# MotoLogger_v3_4_Schematic.net
KiCad netlist of a schematic drawn in EasyEDA
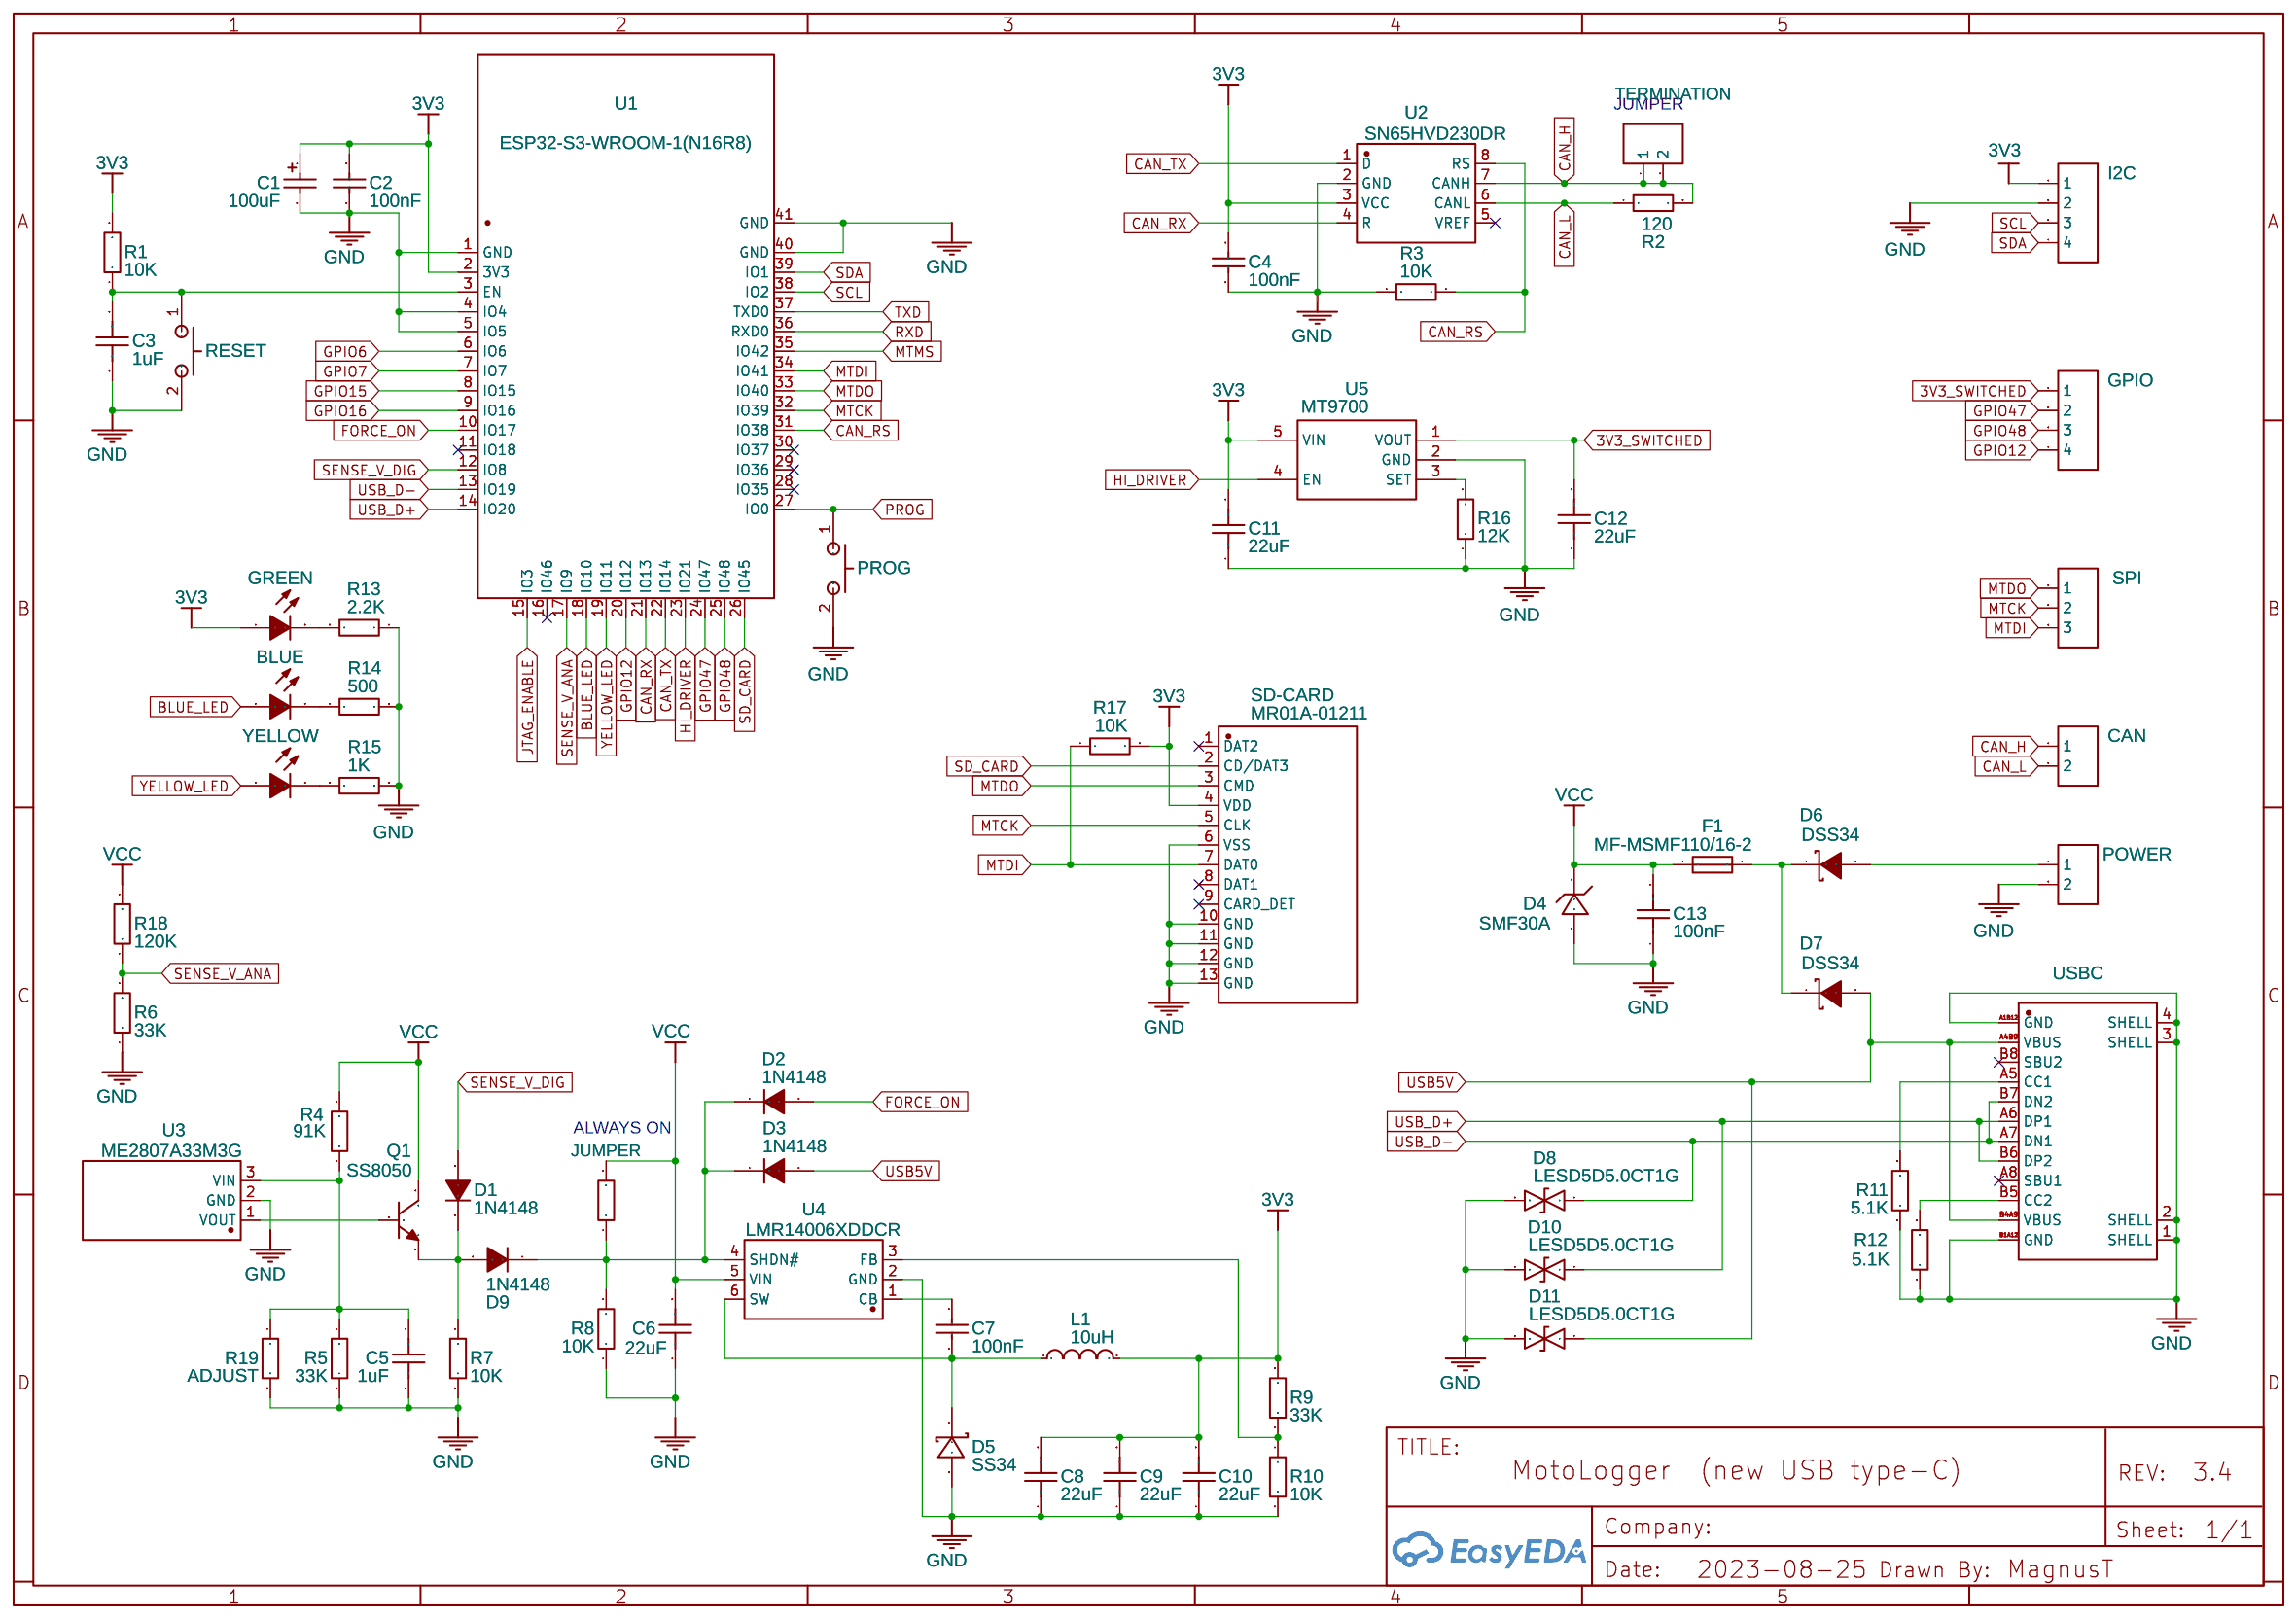
[diagram p0: schematic sheet]

(export (version "E")
  (design (tool "Eeschema 10.0.6"))
  (components
    (comp (ref "BLUE")
      (value "19-217/BHC-ZL1M2RY/3T")
      (fields (field (name "Manufacturer") "EVERLIGHT"))
      (libsource (lib "") (part "19-217/BHC-ZL1M2RY/3T"))
    )
    (comp (ref "C1")
      (value "100uF")
      (fields (field (name "Manufacturer Part") "TAJB107K006RNJ") (field (name "Manufacturer") "AVX"))
      (libsource (lib "") (part "TAJB107K006RNJ"))
    )
    (comp (ref "C2")
      (value "100nF")
      (fields (field (name "Manufacturer Part") "CL05B104KO5NNNC") (field (name "Manufacturer") "SAMSUNG"))
      (libsource (lib "") (part "CL05B104KO5NNNC"))
    )
    (comp (ref "C3")
      (value "1uF")
      (fields (field (name "Manufacturer Part") "CL05A105KA5NQNC") (field (name "Manufacturer") "SAMSUNG"))
      (libsource (lib "") (part "CL05A105KA5NQNC_1"))
    )
    (comp (ref "C4")
      (value "100nF")
      (fields (field (name "Manufacturer Part") "CL05B104KO5NNNC") (field (name "Manufacturer") "SAMSUNG"))
      (libsource (lib "") (part "CL05B104KO5NNNC"))
    )
    (comp (ref "C5")
      (value "1uF")
      (fields (field (name "Manufacturer Part") "CL05A105KA5NQNC") (field (name "Manufacturer") "SAMSUNG"))
      (libsource (lib "") (part "CL05A105KA5NQNC"))
    )
    (comp (ref "C6")
      (value "22uF")
      (fields
        (field (name "Manufacturer Part") "CL21A226MAYNNNE")
        (field (name "Manufacturer") "Samsung Electro-Mechanics")
      )
      (libsource (lib "") (part "CL21A226MAYNNNE"))
    )
    (comp (ref "C7")
      (value "100nF")
      (fields (field (name "Manufacturer Part") "CL05B104KO5NNNC") (field (name "Manufacturer") "SAMSUNG"))
      (libsource (lib "") (part "CL05B104KO5NNNC"))
    )
    (comp (ref "C8")
      (value "22uF")
      (fields (field (name "Manufacturer Part") "CL10A226MQ8NRNC") (field (name "Manufacturer") "SAMSUNG"))
      (libsource (lib "") (part "CL10A226MQ8NRNC"))
    )
    (comp (ref "C9")
      (value "22uF")
      (fields (field (name "Manufacturer Part") "CL10A226MQ8NRNC") (field (name "Manufacturer") "SAMSUNG"))
      (libsource (lib "") (part "CL10A226MQ8NRNC"))
    )
    (comp (ref "C10")
      (value "22uF")
      (fields (field (name "Manufacturer Part") "CL10A226MQ8NRNC") (field (name "Manufacturer") "SAMSUNG"))
      (libsource (lib "") (part "CL10A226MQ8NRNC"))
    )
    (comp (ref "C11")
      (value "22uF")
      (fields (field (name "Manufacturer Part") "CL10A226MQ8NRNC") (field (name "Manufacturer") "SAMSUNG"))
      (libsource (lib "") (part "CL10A226MQ8NRNC"))
    )
    (comp (ref "C12")
      (value "22uF")
      (fields (field (name "Manufacturer Part") "CL10A226MQ8NRNC") (field (name "Manufacturer") "SAMSUNG"))
      (libsource (lib "") (part "CL10A226MQ8NRNC"))
    )
    (comp (ref "C13")
      (value "100nF")
      (fields
        (field (name "Manufacturer Part") "CL05B104KB54PNC")
        (field (name "Manufacturer") "Samsung Electro-Mechanics")
      )
      (libsource (lib "") (part "CL05B104KB54PNC"))
    )
    (comp (ref "CAN") (value "HDR-M-2.54_1x2") (libsource (lib "") (part "HDR-M-2.54_1x2")))
    (comp (ref "D1")
      (value "1N4148")
      (fields (field (name "Manufacturer Part") "1N4148WS T4") (field (name "Manufacturer") "CJ"))
      (libsource (lib "") (part "1N4148WS T4_2"))
    )
    (comp (ref "D2")
      (value "1N4148")
      (fields (field (name "Manufacturer Part") "1N4148WS T4") (field (name "Manufacturer") "CJ"))
      (libsource (lib "") (part "1N4148WS T4_1"))
    )
    (comp (ref "D3")
      (value "1N4148")
      (fields (field (name "Manufacturer Part") "1N4148WS T4") (field (name "Manufacturer") "CJ"))
      (libsource (lib "") (part "1N4148WS T4_1"))
    )
    (comp (ref "D4")
      (value "SMF30A")
      (fields (field (name "Manufacturer") "DOWO"))
      (libsource (lib "") (part "SMF30A_C366558"))
    )
    (comp (ref "D5")
      (value "SS34")
      (fields (field (name "Manufacturer") "MDD"))
      (libsource (lib "") (part "SS34_C8678"))
    )
    (comp (ref "D6")
      (value "DSS34")
      (fields (field (name "Manufacturer") "STARSEA"))
      (libsource (lib "") (part "DSS34"))
    )
    (comp (ref "D7")
      (value "DSS34")
      (fields (field (name "Manufacturer") "STARSEA"))
      (libsource (lib "") (part "DSS34"))
    )
    (comp (ref "D8")
      (value "LESD5D5.0CT1G")
      (fields (field (name "Manufacturer") "Leshan Radio"))
      (libsource (lib "") (part "LESD5D5.0CT1G"))
    )
    (comp (ref "D9")
      (value "1N4148")
      (fields (field (name "Manufacturer Part") "1N4148WS T4") (field (name "Manufacturer") "CJ"))
      (libsource (lib "") (part "1N4148WS T4"))
    )
    (comp (ref "D10")
      (value "LESD5D5.0CT1G")
      (fields (field (name "Manufacturer") "Leshan Radio"))
      (libsource (lib "") (part "LESD5D5.0CT1G"))
    )
    (comp (ref "D11")
      (value "LESD5D5.0CT1G")
      (fields (field (name "Manufacturer") "Leshan Radio"))
      (libsource (lib "") (part "LESD5D5.0CT1G"))
    )
    (comp (ref "F1")
      (value "MF-MSMF110/16-2")
      (fields (field (name "Manufacturer") "BOURNS"))
      (libsource (lib "") (part "MF-MSMF110/16-2"))
    )
    (comp (ref "GPIO") (value "HDR-M-2.54_1x4") (libsource (lib "") (part "HDR-M-2.54_1x4")))
    (comp (ref "GREEN")
      (value "19-217/GHC-YR1S2/3T")
      (fields (field (name "Manufacturer") "EVERLIGHT"))
      (libsource (lib "") (part "19-217/GHC-YR1S2/3T"))
    )
    (comp (ref "I2C") (value "HDR-M-2.54_1x4") (libsource (lib "") (part "HDR-M-2.54_1x4_1")))
    (comp (ref "JUMPER") (value "-") (libsource (lib "") (part "0402WGF3092TCE")))
    (comp (ref "L1")
      (value "10uH")
      (fields
        (field (name "Manufacturer Part") "SLP6028S100MTT")
        (field (name "Manufacturer") "Sunltech Tech")
      )
      (libsource (lib "") (part "SLP6028S100MTT"))
    )
    (comp (ref "POWER") (value "HDR-M-2.54_1x2") (libsource (lib "") (part "HDR-M-2.54_1x2_2")))
    (comp (ref "PROG")
      (value "GT-TC029B-H025-L1N")
      (fields (field (name "Manufacturer") "G-Switch"))
      (libsource (lib "") (part "GT-TC029B-H025-L1N_1"))
    )
    (comp (ref "Q1")
      (value "SS8050")
      (fields (field (name "Manufacturer") "CJ"))
      (libsource (lib "") (part "SS8050_C2150"))
    )
    (comp (ref "R1")
      (value "10K")
      (fields (field (name "Manufacturer Part") "0402WGF1002TCE") (field (name "Manufacturer") "UniOhm"))
      (libsource (lib "") (part "0402WGF1002TCE_2"))
    )
    (comp (ref "R2")
      (value "120")
      (fields (field (name "Manufacturer Part") "RTT061200FTP") (field (name "Manufacturer") "RALEC"))
      (libsource (lib "") (part "RTT061200FTP"))
    )
    (comp (ref "R3")
      (value "10K")
      (fields (field (name "Manufacturer Part") "0402WGF1002TCE") (field (name "Manufacturer") "UniOhm"))
      (libsource (lib "") (part "0402WGF1002TCE"))
    )
    (comp (ref "R4")
      (value "91K")
      (fields (field (name "Manufacturer Part") "0402WGF9102TCE") (field (name "Manufacturer") "UniOhm"))
      (libsource (lib "") (part "0402WGF9102TCE_1"))
    )
    (comp (ref "R5")
      (value "33K")
      (fields (field (name "Manufacturer Part") "0402WGF3302TCE") (field (name "Manufacturer") "UniOhm"))
      (libsource (lib "") (part "0402WGF3302TCE"))
    )
    (comp (ref "R6")
      (value "33K")
      (fields (field (name "Manufacturer Part") "0402WGF3302TCE") (field (name "Manufacturer") "UniOhm"))
      (libsource (lib "") (part "0402WGF3302TCE"))
    )
    (comp (ref "R7")
      (value "10K")
      (fields (field (name "Manufacturer Part") "0402WGF1002TCE") (field (name "Manufacturer") "UniOhm"))
      (libsource (lib "") (part "0402WGF1002TCE_2"))
    )
    (comp (ref "R8")
      (value "10K")
      (fields (field (name "Manufacturer Part") "0402WGF1002TCE") (field (name "Manufacturer") "UniOhm"))
      (libsource (lib "") (part "0402WGF1002TCE_2"))
    )
    (comp (ref "R9")
      (value "33K")
      (fields (field (name "Manufacturer Part") "0402WGF3302TCE") (field (name "Manufacturer") "UniOhm"))
      (libsource (lib "") (part "0402WGF3302TCE"))
    )
    (comp (ref "R10")
      (value "10K")
      (fields (field (name "Manufacturer Part") "0402WGF1002TCE") (field (name "Manufacturer") "UniOhm"))
      (libsource (lib "") (part "0402WGF1002TCE_1"))
    )
    (comp (ref "R11")
      (value "5.1K")
      (fields (field (name "Manufacturer Part") "0402WGF5101TCE") (field (name "Manufacturer") "UniOhm"))
      (libsource (lib "") (part "0402WGF5101TCE"))
    )
    (comp (ref "R12")
      (value "5.1K")
      (fields (field (name "Manufacturer Part") "0402WGF5101TCE") (field (name "Manufacturer") "UniOhm"))
      (libsource (lib "") (part "0402WGF5101TCE"))
    )
    (comp (ref "R13")
      (value "2.2K")
      (fields (field (name "Manufacturer Part") "0402WGF2201TCE") (field (name "Manufacturer") "UniOhm"))
      (libsource (lib "") (part "0402WGF2201TCE"))
    )
    (comp (ref "R14")
      (value "500")
      (fields (field (name "Manufacturer Part") "0402WGF4700TCE") (field (name "Manufacturer") "UniOhm"))
      (libsource (lib "") (part "0402WGF1001TCE"))
    )
    (comp (ref "R15")
      (value "1K")
      (fields (field (name "Manufacturer Part") "0402WGF1001TCE") (field (name "Manufacturer") "UniOhm"))
      (libsource (lib "") (part "0402WGF1001TCE"))
    )
    (comp (ref "R16")
      (value "12K")
      (fields (field (name "Manufacturer Part") "0402WGF1202TCE") (field (name "Manufacturer") "UniOhm"))
      (libsource (lib "") (part "0402WGF1202TCE"))
    )
    (comp (ref "R17")
      (value "10K")
      (fields (field (name "Manufacturer Part") "0402WGF1002TCE") (field (name "Manufacturer") "UniOhm"))
      (libsource (lib "") (part "0402WGF1002TCE"))
    )
    (comp (ref "R18")
      (value "120K")
      (fields (field (name "Manufacturer Part") "0402WGF1203TCE") (field (name "Manufacturer") "UniOhm"))
      (libsource (lib "") (part "0402WGF1203TCE"))
    )
    (comp (ref "R19")
      (value "ADJUST")
      (fields (field (name "Manufacturer Part") "0402WGF9102TCE") (field (name "Manufacturer") "UniOhm"))
      (libsource (lib "") (part "0402WGF9102TCE"))
    )
    (comp (ref "RESET")
      (value "GT-TC029B-H025-L1N")
      (fields (field (name "Manufacturer") "G-Switch"))
      (libsource (lib "") (part "GT-TC029B-H025-L1N"))
    )
    (comp (ref "SD-CARD")
      (value "MR01A-01211")
      (fields (field (name "Manufacturer") "ATOM(爱特姆)"))
      (libsource (lib "") (part "MR01A-01211"))
    )
    (comp (ref "SPI") (value "HDR-M-2.54_1x3") (libsource (lib "") (part "HDR-M-2.54_1x3")))
    (comp (ref "TERMINATION") (value "HDR-M-2.54_1x2") (libsource (lib "") (part "HDR-M-2.54_1x2_1")))
    (comp (ref "U1")
      (value "ESP32-S3-WROOM-1(N16R8)")
      (fields (field (name "Manufacturer") "ESPRESSIF(乐鑫)"))
      (libsource (lib "") (part "ESP32-S3-WROOM-1(N16R8)"))
    )
    (comp (ref "U2")
      (value "SN65HVD230DR")
      (fields (field (name "Manufacturer") "TI"))
      (libsource (lib "") (part "SN65HVD230DR"))
    )
    (comp (ref "U3")
      (value "ME2807A33M3G")
      (fields (field (name "Manufacturer") "Nanjing Micro One Elec"))
      (libsource (lib "") (part "ME2807A33M3G"))
    )
    (comp (ref "U4")
      (value "LMR14006XDDCR")
      (fields (field (name "Manufacturer") "Texas Instruments"))
      (libsource (lib "") (part "LMR14006XDDCR"))
    )
    (comp (ref "U5")
      (value "MT9700")
      (fields (field (name "Manufacturer") "AEROSEMI"))
      (libsource (lib "") (part "MT9700"))
    )
    (comp (ref "USBC")
      (value "GT-USB-7010ASV")
      (fields (field (name "Manufacturer") "G-Switch(品赞)"))
      (libsource (lib "") (part "GT-USB-7010ASV"))
    )
    (comp (ref "YELLOW")
      (value "19-213/Y2C-CQ2R2L/3T(CY)")
      (fields (field (name "Manufacturer") "EVERLIGHT"))
      (libsource (lib "") (part "19-213/Y2C-CQ2R2L/3T(CY)"))
    )
  )
  (nets
    (net (code "1") (name "3V3") (class "Default")
      (node (ref "C1") (pin "1") (pinfunction "1_1") (pintype "input"))
      (node (ref "C10") (pin "2") (pinfunction "2_2") (pintype "unspecified"))
      (node (ref "C11") (pin "2") (pinfunction "2_2") (pintype "unspecified"))
      (node (ref "C2") (pin "2") (pinfunction "2_2") (pintype "input"))
      (node (ref "C4") (pin "2") (pinfunction "2_2") (pintype "input"))
      (node (ref "C8") (pin "2") (pinfunction "2_2") (pintype "unspecified"))
      (node (ref "C9") (pin "2") (pinfunction "2_2") (pintype "unspecified"))
      (node (ref "GREEN") (pin "1") (pinfunction "A_1") (pintype "input"))
      (node (ref "I2C") (pin "1") (pinfunction "1_1") (pintype "unspecified"))
      (node (ref "L1") (pin "2") (pinfunction "2_2") (pintype "unspecified"))
      (node (ref "R1") (pin "2") (pinfunction "2_2") (pintype "input"))
      (node (ref "R17") (pin "2") (pinfunction "2_2") (pintype "input"))
      (node (ref "R9") (pin "2") (pinfunction "2_2") (pintype "input"))
      (node (ref "SD-CARD") (pin "4") (pinfunction "VDD_4") (pintype "unspecified"))
      (node (ref "U1") (pin "2") (pinfunction "3V3_2") (pintype "unspecified"))
      (node (ref "U2") (pin "3") (pinfunction "VCC_3") (pintype "unspecified"))
      (node (ref "U5") (pin "5") (pinfunction "VIN_5") (pintype "unspecified"))
    )
    (net (code "2") (name "3V3_SWITCHED") (class "Default")
      (node (ref "C12") (pin "2") (pinfunction "2_2") (pintype "unspecified"))
      (node (ref "GPIO") (pin "1") (pinfunction "1_1") (pintype "unspecified"))
      (node (ref "U5") (pin "1") (pinfunction "VOUT_1") (pintype "unspecified"))
    )
    (net (code "3") (name "BLUE_LED") (class "Default")
      (node (ref "BLUE") (pin "1") (pinfunction "A_1") (pintype "input"))
      (node (ref "U1") (pin "18") (pinfunction "IO10_18") (pintype "unspecified"))
    )
    (net (code "4") (name "CAN_H") (class "Default")
      (node (ref "CAN") (pin "1") (pinfunction "1_1") (pintype "unspecified"))
      (node (ref "R2") (pin "2") (pinfunction "2_2") (pintype "unspecified"))
      (node (ref "TERMINATION") (pin "1") (pinfunction "1_1") (pintype "unspecified"))
      (node (ref "TERMINATION") (pin "2") (pinfunction "2_2") (pintype "unspecified"))
      (node (ref "U2") (pin "7") (pinfunction "CANH_7") (pintype "unspecified"))
    )
    (net (code "5") (name "CAN_L") (class "Default")
      (node (ref "CAN") (pin "2") (pinfunction "2_2") (pintype "unspecified"))
      (node (ref "R2") (pin "1") (pinfunction "1_1") (pintype "unspecified"))
      (node (ref "U2") (pin "6") (pinfunction "CANL_6") (pintype "unspecified"))
    )
    (net (code "6") (name "CAN_RS") (class "Default")
      (node (ref "R3") (pin "2") (pinfunction "2_2") (pintype "input"))
      (node (ref "U1") (pin "31") (pinfunction "IO38_31") (pintype "unspecified"))
      (node (ref "U2") (pin "8") (pinfunction "RS_8") (pintype "unspecified"))
    )
    (net (code "7") (name "CAN_RX") (class "Default")
      (node (ref "U1") (pin "21") (pinfunction "IO13_21") (pintype "unspecified"))
      (node (ref "U2") (pin "4") (pinfunction "R_4") (pintype "unspecified"))
    )
    (net (code "8") (name "CAN_TX") (class "Default")
      (node (ref "U1") (pin "22") (pinfunction "IO14_22") (pintype "unspecified"))
      (node (ref "U2") (pin "1") (pinfunction "D_1") (pintype "unspecified"))
    )
    (net (code "9") (name "FORCE_ON") (class "Default")
      (node (ref "D2") (pin "2") (pinfunction "A_2") (pintype "unspecified"))
      (node (ref "U1") (pin "10") (pinfunction "IO17_10") (pintype "unspecified"))
    )
    (net (code "10") (name "GND") (class "Default")
      (node (ref "C1") (pin "2") (pinfunction "2_2") (pintype "input"))
      (node (ref "C10") (pin "1") (pinfunction "1_1") (pintype "unspecified"))
      (node (ref "C11") (pin "1") (pinfunction "1_1") (pintype "unspecified"))
      (node (ref "C12") (pin "1") (pinfunction "1_1") (pintype "unspecified"))
      (node (ref "C13") (pin "1") (pinfunction "1_1") (pintype "unspecified"))
      (node (ref "C2") (pin "1") (pinfunction "1_1") (pintype "input"))
      (node (ref "C3") (pin "1") (pinfunction "1_1") (pintype "unspecified"))
      (node (ref "C4") (pin "1") (pinfunction "1_1") (pintype "input"))
      (node (ref "C5") (pin "1") (pinfunction "1_1") (pintype "unspecified"))
      (node (ref "C6") (pin "1") (pinfunction "1_1") (pintype "unspecified"))
      (node (ref "C8") (pin "1") (pinfunction "1_1") (pintype "unspecified"))
      (node (ref "C9") (pin "1") (pinfunction "1_1") (pintype "unspecified"))
      (node (ref "D10") (pin "2") (pinfunction "2_2") (pintype "unspecified"))
      (node (ref "D11") (pin "2") (pinfunction "2_2") (pintype "unspecified"))
      (node (ref "D4") (pin "2") (pinfunction "2_2") (pintype "unspecified"))
      (node (ref "D5") (pin "2") (pinfunction "A_2") (pintype "unspecified"))
      (node (ref "D8") (pin "2") (pinfunction "2_2") (pintype "unspecified"))
      (node (ref "I2C") (pin "2") (pinfunction "2_2") (pintype "unspecified"))
      (node (ref "POWER") (pin "2") (pinfunction "2_2") (pintype "unspecified"))
      (node (ref "PROG") (pin "2") (pinfunction "2_2") (pintype "unspecified"))
      (node (ref "R10") (pin "2") (pinfunction "2_2") (pintype "input"))
      (node (ref "R11") (pin "1") (pinfunction "1_1") (pintype "input"))
      (node (ref "R12") (pin "1") (pinfunction "1_1") (pintype "input"))
      (node (ref "R13") (pin "1") (pinfunction "1_1") (pintype "input"))
      (node (ref "R14") (pin "2") (pinfunction "2_2") (pintype "input"))
      (node (ref "R15") (pin "2") (pinfunction "2_2") (pintype "input"))
      (node (ref "R16") (pin "1") (pinfunction "1_1") (pintype "input"))
      (node (ref "R19") (pin "2") (pinfunction "2_2") (pintype "input"))
      (node (ref "R3") (pin "1") (pinfunction "1_1") (pintype "input"))
      (node (ref "R5") (pin "1") (pinfunction "1_1") (pintype "input"))
      (node (ref "R6") (pin "1") (pinfunction "1_1") (pintype "input"))
      (node (ref "R7") (pin "1") (pinfunction "1_1") (pintype "input"))
      (node (ref "R8") (pin "1") (pinfunction "1_1") (pintype "input"))
      (node (ref "RESET") (pin "2") (pinfunction "2_2") (pintype "unspecified"))
      (node (ref "SD-CARD") (pin "10") (pinfunction "GND_10") (pintype "unspecified"))
      (node (ref "SD-CARD") (pin "11") (pinfunction "GND_11") (pintype "unspecified"))
      (node (ref "SD-CARD") (pin "12") (pinfunction "GND_12") (pintype "unspecified"))
      (node (ref "SD-CARD") (pin "13") (pinfunction "GND_13") (pintype "unspecified"))
      (node (ref "SD-CARD") (pin "6") (pinfunction "VSS_6") (pintype "unspecified"))
      (node (ref "U1") (pin "1") (pinfunction "GND_1") (pintype "unspecified"))
      (node (ref "U1") (pin "4") (pinfunction "IO4_4") (pintype "unspecified"))
      (node (ref "U1") (pin "40") (pinfunction "GND_40") (pintype "unspecified"))
      (node (ref "U1") (pin "41") (pinfunction "GND_41") (pintype "unspecified"))
      (node (ref "U1") (pin "5") (pinfunction "IO5_5") (pintype "unspecified"))
      (node (ref "U2") (pin "2") (pinfunction "GND_2") (pintype "unspecified"))
      (node (ref "U3") (pin "2") (pinfunction "GND_2") (pintype "unspecified"))
      (node (ref "U4") (pin "2") (pinfunction "GND_2") (pintype "unspecified"))
      (node (ref "U5") (pin "2") (pinfunction "GND_2") (pintype "unspecified"))
      (node (ref "USBC") (pin "1") (pinfunction "SHELL_1") (pintype "unspecified"))
      (node (ref "USBC") (pin "2") (pinfunction "SHELL_2") (pintype "unspecified"))
      (node (ref "USBC") (pin "3") (pinfunction "SHELL_3") (pintype "unspecified"))
      (node (ref "USBC") (pin "4") (pinfunction "SHELL_4") (pintype "unspecified"))
      (node (ref "USBC") (pin "A1B12") (pinfunction "GND_A1B12") (pintype "unspecified"))
      (node (ref "USBC") (pin "B1A12") (pinfunction "GND_B1A12") (pintype "unspecified"))
    )
    (net (code "11") (name "GPIO6") (class "Default")
      (node (ref "U1") (pin "6") (pinfunction "IO6_6") (pintype "unspecified"))
    )
    (net (code "12") (name "GPIO7") (class "Default")
      (node (ref "U1") (pin "7") (pinfunction "IO7_7") (pintype "unspecified"))
    )
    (net (code "13") (name "GPIO12") (class "Default")
      (node (ref "GPIO") (pin "4") (pinfunction "4_4") (pintype "unspecified"))
      (node (ref "U1") (pin "20") (pinfunction "IO12_20") (pintype "unspecified"))
    )
    (net (code "14") (name "GPIO15") (class "Default")
      (node (ref "U1") (pin "8") (pinfunction "IO15_8") (pintype "unspecified"))
    )
    (net (code "15") (name "GPIO16") (class "Default")
      (node (ref "U1") (pin "9") (pinfunction "IO16_9") (pintype "unspecified"))
    )
    (net (code "16") (name "GPIO47") (class "Default")
      (node (ref "GPIO") (pin "2") (pinfunction "2_2") (pintype "unspecified"))
      (node (ref "U1") (pin "24") (pinfunction "IO47_24") (pintype "unspecified"))
    )
    (net (code "17") (name "GPIO48") (class "Default")
      (node (ref "GPIO") (pin "3") (pinfunction "3_3") (pintype "unspecified"))
      (node (ref "U1") (pin "25") (pinfunction "IO48_25") (pintype "unspecified"))
    )
    (net (code "18") (name "HI_DRIVER") (class "Default")
      (node (ref "U1") (pin "23") (pinfunction "IO21_23") (pintype "unspecified"))
      (node (ref "U5") (pin "4") (pinfunction "EN_4") (pintype "unspecified"))
    )
    (net (code "19") (name "JTAG_ENABLE") (class "Default")
      (node (ref "U1") (pin "15") (pinfunction "IO3_15") (pintype "unspecified"))
    )
    (net (code "20") (name "MTCK") (class "Default")
      (node (ref "SD-CARD") (pin "5") (pinfunction "CLK_5") (pintype "unspecified"))
      (node (ref "SPI") (pin "2") (pinfunction "2_2") (pintype "input"))
      (node (ref "U1") (pin "32") (pinfunction "IO39_32") (pintype "unspecified"))
    )
    (net (code "21") (name "MTDI") (class "Default")
      (node (ref "R17") (pin "1") (pinfunction "1_1") (pintype "input"))
      (node (ref "SD-CARD") (pin "7") (pinfunction "DAT0_7") (pintype "unspecified"))
      (node (ref "SPI") (pin "3") (pinfunction "3_3") (pintype "input"))
      (node (ref "U1") (pin "34") (pinfunction "IO41_34") (pintype "unspecified"))
    )
    (net (code "22") (name "MTDO") (class "Default")
      (node (ref "SD-CARD") (pin "3") (pinfunction "CMD_3") (pintype "unspecified"))
      (node (ref "SPI") (pin "1") (pinfunction "1_1") (pintype "input"))
      (node (ref "U1") (pin "33") (pinfunction "IO40_33") (pintype "unspecified"))
    )
    (net (code "23") (name "MTMS") (class "Default")
      (node (ref "U1") (pin "35") (pinfunction "IO42_35") (pintype "unspecified"))
    )
    (net (code "24") (name "Net-(BLUE-C)") (class "Default")
      (node (ref "BLUE") (pin "2") (pinfunction "C_2") (pintype "input"))
      (node (ref "R14") (pin "1") (pinfunction "1_1") (pintype "input"))
    )
    (net (code "25") (name "Net-(D1-K)") (class "Default")
      (node (ref "D1") (pin "1") (pinfunction "K_1") (pintype "unspecified"))
      (node (ref "D9") (pin "2") (pinfunction "A_2") (pintype "unspecified"))
      (node (ref "Q1") (pin "2") (pinfunction "E_2") (pintype "unspecified"))
      (node (ref "R7") (pin "2") (pinfunction "2_2") (pintype "input"))
    )
    (net (code "26") (name "Net-(D2-K)") (class "Default")
      (node (ref "D2") (pin "1") (pinfunction "K_1") (pintype "unspecified"))
      (node (ref "D3") (pin "1") (pinfunction "K_1") (pintype "unspecified"))
      (node (ref "D9") (pin "1") (pinfunction "K_1") (pintype "unspecified"))
      (node (ref "JUMPER") (pin "1") (pinfunction "1_1") (pintype "unspecified"))
      (node (ref "R8") (pin "2") (pinfunction "2_2") (pintype "input"))
      (node (ref "U4") (pin "4") (pinfunction "SHDN#_4") (pintype "unspecified"))
    )
    (net (code "27") (name "Net-(D5-K)") (class "Default")
      (node (ref "C7") (pin "1") (pinfunction "1_1") (pintype "input"))
      (node (ref "D5") (pin "1") (pinfunction "K_1") (pintype "unspecified"))
      (node (ref "L1") (pin "1") (pinfunction "1_1") (pintype "unspecified"))
      (node (ref "U4") (pin "6") (pinfunction "SW_6") (pintype "unspecified"))
    )
    (net (code "28") (name "Net-(D6-A)") (class "Default")
      (node (ref "D6") (pin "2") (pinfunction "A_2") (pintype "unspecified"))
      (node (ref "POWER") (pin "1") (pinfunction "1_1") (pintype "unspecified"))
    )
    (net (code "29") (name "Net-(D6-K)") (class "Default")
      (node (ref "D6") (pin "1") (pinfunction "K_1") (pintype "unspecified"))
      (node (ref "D7") (pin "1") (pinfunction "K_1") (pintype "unspecified"))
      (node (ref "F1") (pin "2") (pinfunction "2_2") (pintype "unspecified"))
    )
    (net (code "30") (name "Net-(GREEN-C)") (class "Default")
      (node (ref "GREEN") (pin "2") (pinfunction "C_2") (pintype "input"))
      (node (ref "R13") (pin "2") (pinfunction "2_2") (pintype "input"))
    )
    (net (code "31") (name "Net-(Q1-B)") (class "Default")
      (node (ref "Q1") (pin "1") (pinfunction "B_1") (pintype "unspecified"))
      (node (ref "U3") (pin "1") (pinfunction "VOUT_1") (pintype "unspecified"))
    )
    (net (code "32") (name "Net-(U1-EN)") (class "Default")
      (node (ref "C3") (pin "2") (pinfunction "2_2") (pintype "unspecified"))
      (node (ref "R1") (pin "1") (pinfunction "1_1") (pintype "input"))
      (node (ref "RESET") (pin "1") (pinfunction "1_1") (pintype "unspecified"))
      (node (ref "U1") (pin "3") (pinfunction "EN_3") (pintype "unspecified"))
    )
    (net (code "33") (name "Net-(U3-VIN)") (class "Default")
      (node (ref "C5") (pin "2") (pinfunction "2_2") (pintype "unspecified"))
      (node (ref "R19") (pin "1") (pinfunction "1_1") (pintype "input"))
      (node (ref "R4") (pin "1") (pinfunction "1_1") (pintype "input"))
      (node (ref "R5") (pin "2") (pinfunction "2_2") (pintype "input"))
      (node (ref "U3") (pin "3") (pinfunction "VIN_3") (pintype "unspecified"))
    )
    (net (code "34") (name "Net-(U4-CB)") (class "Default")
      (node (ref "C7") (pin "2") (pinfunction "2_2") (pintype "input"))
      (node (ref "U4") (pin "1") (pinfunction "CB_1") (pintype "unspecified"))
    )
    (net (code "35") (name "Net-(U4-FB)") (class "Default")
      (node (ref "R10") (pin "1") (pinfunction "1_1") (pintype "input"))
      (node (ref "R9") (pin "1") (pinfunction "1_1") (pintype "input"))
      (node (ref "U4") (pin "3") (pinfunction "FB_3") (pintype "unspecified"))
    )
    (net (code "36") (name "Net-(U5-SET)") (class "Default")
      (node (ref "R16") (pin "2") (pinfunction "2_2") (pintype "input"))
      (node (ref "U5") (pin "3") (pinfunction "SET_3") (pintype "unspecified"))
    )
    (net (code "37") (name "Net-(USBC-CC1)") (class "Default")
      (node (ref "R11") (pin "2") (pinfunction "2_2") (pintype "input"))
      (node (ref "USBC") (pin "A5") (pinfunction "CC1_A5") (pintype "unspecified"))
    )
    (net (code "38") (name "Net-(USBC-CC2)") (class "Default")
      (node (ref "R12") (pin "2") (pinfunction "2_2") (pintype "input"))
      (node (ref "USBC") (pin "B5") (pinfunction "CC2_B5") (pintype "unspecified"))
    )
    (net (code "39") (name "Net-(YELLOW-C)") (class "Default")
      (node (ref "R15") (pin "1") (pinfunction "1_1") (pintype "input"))
      (node (ref "YELLOW") (pin "2") (pinfunction "C_2") (pintype "input"))
    )
    (net (code "40") (name "PROG") (class "Default")
      (node (ref "PROG") (pin "1") (pinfunction "1_1") (pintype "unspecified"))
      (node (ref "U1") (pin "27") (pinfunction "IO0_27") (pintype "unspecified"))
    )
    (net (code "41") (name "RXD") (class "Default")
      (node (ref "U1") (pin "36") (pinfunction "RXD0_36") (pintype "unspecified"))
    )
    (net (code "42") (name "SCL") (class "Default")
      (node (ref "I2C") (pin "3") (pinfunction "3_3") (pintype "unspecified"))
      (node (ref "U1") (pin "38") (pinfunction "IO2_38") (pintype "unspecified"))
    )
    (net (code "43") (name "SDA") (class "Default")
      (node (ref "I2C") (pin "4") (pinfunction "4_4") (pintype "unspecified"))
      (node (ref "U1") (pin "39") (pinfunction "IO1_39") (pintype "unspecified"))
    )
    (net (code "44") (name "SD_CARD") (class "Default")
      (node (ref "SD-CARD") (pin "2") (pinfunction "CD/DAT3_2") (pintype "unspecified"))
      (node (ref "U1") (pin "26") (pinfunction "IO45_26") (pintype "unspecified"))
    )
    (net (code "45") (name "SENSE_V_ANA") (class "Default")
      (node (ref "R18") (pin "1") (pinfunction "1_1") (pintype "input"))
      (node (ref "R6") (pin "2") (pinfunction "2_2") (pintype "input"))
      (node (ref "U1") (pin "17") (pinfunction "IO9_17") (pintype "unspecified"))
    )
    (net (code "46") (name "SENSE_V_DIG") (class "Default")
      (node (ref "D1") (pin "2") (pinfunction "A_2") (pintype "unspecified"))
      (node (ref "U1") (pin "12") (pinfunction "IO8_12") (pintype "unspecified"))
    )
    (net (code "47") (name "TXD") (class "Default")
      (node (ref "U1") (pin "37") (pinfunction "TXD0_37") (pintype "unspecified"))
    )
    (net (code "48") (name "USB5V") (class "Default")
      (node (ref "D11") (pin "1") (pinfunction "1_1") (pintype "unspecified"))
      (node (ref "D3") (pin "2") (pinfunction "A_2") (pintype "unspecified"))
      (node (ref "D7") (pin "2") (pinfunction "A_2") (pintype "unspecified"))
      (node (ref "USBC") (pin "A4B9") (pinfunction "VBUS_A4B9") (pintype "unspecified"))
      (node (ref "USBC") (pin "B4A9") (pinfunction "VBUS_B4A9") (pintype "unspecified"))
    )
    (net (code "49") (name "USB_D+") (class "Default")
      (node (ref "D10") (pin "1") (pinfunction "1_1") (pintype "unspecified"))
      (node (ref "U1") (pin "14") (pinfunction "IO20_14") (pintype "unspecified"))
      (node (ref "USBC") (pin "A6") (pinfunction "DP1_A6") (pintype "unspecified"))
      (node (ref "USBC") (pin "B6") (pinfunction "DP2_B6") (pintype "unspecified"))
    )
    (net (code "50") (name "USB_D-") (class "Default")
      (node (ref "D8") (pin "1") (pinfunction "1_1") (pintype "unspecified"))
      (node (ref "U1") (pin "13") (pinfunction "IO19_13") (pintype "unspecified"))
      (node (ref "USBC") (pin "A7") (pinfunction "DN1_A7") (pintype "unspecified"))
      (node (ref "USBC") (pin "B7") (pinfunction "DN2_B7") (pintype "unspecified"))
    )
    (net (code "51") (name "VCC") (class "Default")
      (node (ref "C13") (pin "2") (pinfunction "2_2") (pintype "unspecified"))
      (node (ref "C6") (pin "2") (pinfunction "2_2") (pintype "unspecified"))
      (node (ref "D4") (pin "1") (pinfunction "1_1") (pintype "unspecified"))
      (node (ref "F1") (pin "1") (pinfunction "1_1") (pintype "unspecified"))
      (node (ref "JUMPER") (pin "2") (pinfunction "2_2") (pintype "unspecified"))
      (node (ref "Q1") (pin "3") (pinfunction "C_3") (pintype "unspecified"))
      (node (ref "R18") (pin "2") (pinfunction "2_2") (pintype "input"))
      (node (ref "R4") (pin "2") (pinfunction "2_2") (pintype "input"))
      (node (ref "U4") (pin "5") (pinfunction "VIN_5") (pintype "unspecified"))
    )
    (net (code "52") (name "YELLOW_LED") (class "Default")
      (node (ref "U1") (pin "19") (pinfunction "IO11_19") (pintype "unspecified"))
      (node (ref "YELLOW") (pin "1") (pinfunction "A_1") (pintype "input"))
    )
    (net (code "53") (name "unconnected-(SD-CARD-CARD_DET-Pad9)") (class "Default")
      (node (ref "SD-CARD") (pin "9") (pinfunction "CARD_DET_9") (pintype "unspecified+no_connect"))
    )
    (net (code "54") (name "unconnected-(SD-CARD-DAT1-Pad8)") (class "Default")
      (node (ref "SD-CARD") (pin "8") (pinfunction "DAT1_8") (pintype "unspecified+no_connect"))
    )
    (net (code "55") (name "unconnected-(SD-CARD-DAT2-Pad1)") (class "Default")
      (node (ref "SD-CARD") (pin "1") (pinfunction "DAT2_1") (pintype "unspecified+no_connect"))
    )
    (net (code "56") (name "unconnected-(U1-IO18-Pad11)") (class "Default")
      (node (ref "U1") (pin "11") (pinfunction "IO18_11") (pintype "unspecified+no_connect"))
    )
    (net (code "57") (name "unconnected-(U1-IO35-Pad28)") (class "Default")
      (node (ref "U1") (pin "28") (pinfunction "IO35_28") (pintype "unspecified+no_connect"))
    )
    (net (code "58") (name "unconnected-(U1-IO36-Pad29)") (class "Default")
      (node (ref "U1") (pin "29") (pinfunction "IO36_29") (pintype "unspecified+no_connect"))
    )
    (net (code "59") (name "unconnected-(U1-IO37-Pad30)") (class "Default")
      (node (ref "U1") (pin "30") (pinfunction "IO37_30") (pintype "unspecified+no_connect"))
    )
    (net (code "60") (name "unconnected-(U1-IO46-Pad16)") (class "Default")
      (node (ref "U1") (pin "16") (pinfunction "IO46_16") (pintype "unspecified+no_connect"))
    )
    (net (code "61") (name "unconnected-(U2-VREF-Pad5)") (class "Default")
      (node (ref "U2") (pin "5") (pinfunction "VREF_5") (pintype "unspecified+no_connect"))
    )
    (net (code "62") (name "unconnected-(USBC-SBU1-PadA8)") (class "Default")
      (node (ref "USBC") (pin "A8") (pinfunction "SBU1_A8") (pintype "unspecified+no_connect"))
    )
    (net (code "63") (name "unconnected-(USBC-SBU2-PadB8)") (class "Default")
      (node (ref "USBC") (pin "B8") (pinfunction "SBU2_B8") (pintype "unspecified+no_connect"))
    )
  )
)
